# Deckelplatine.net
KiCad netlist of a schematic drawn in EAGLE
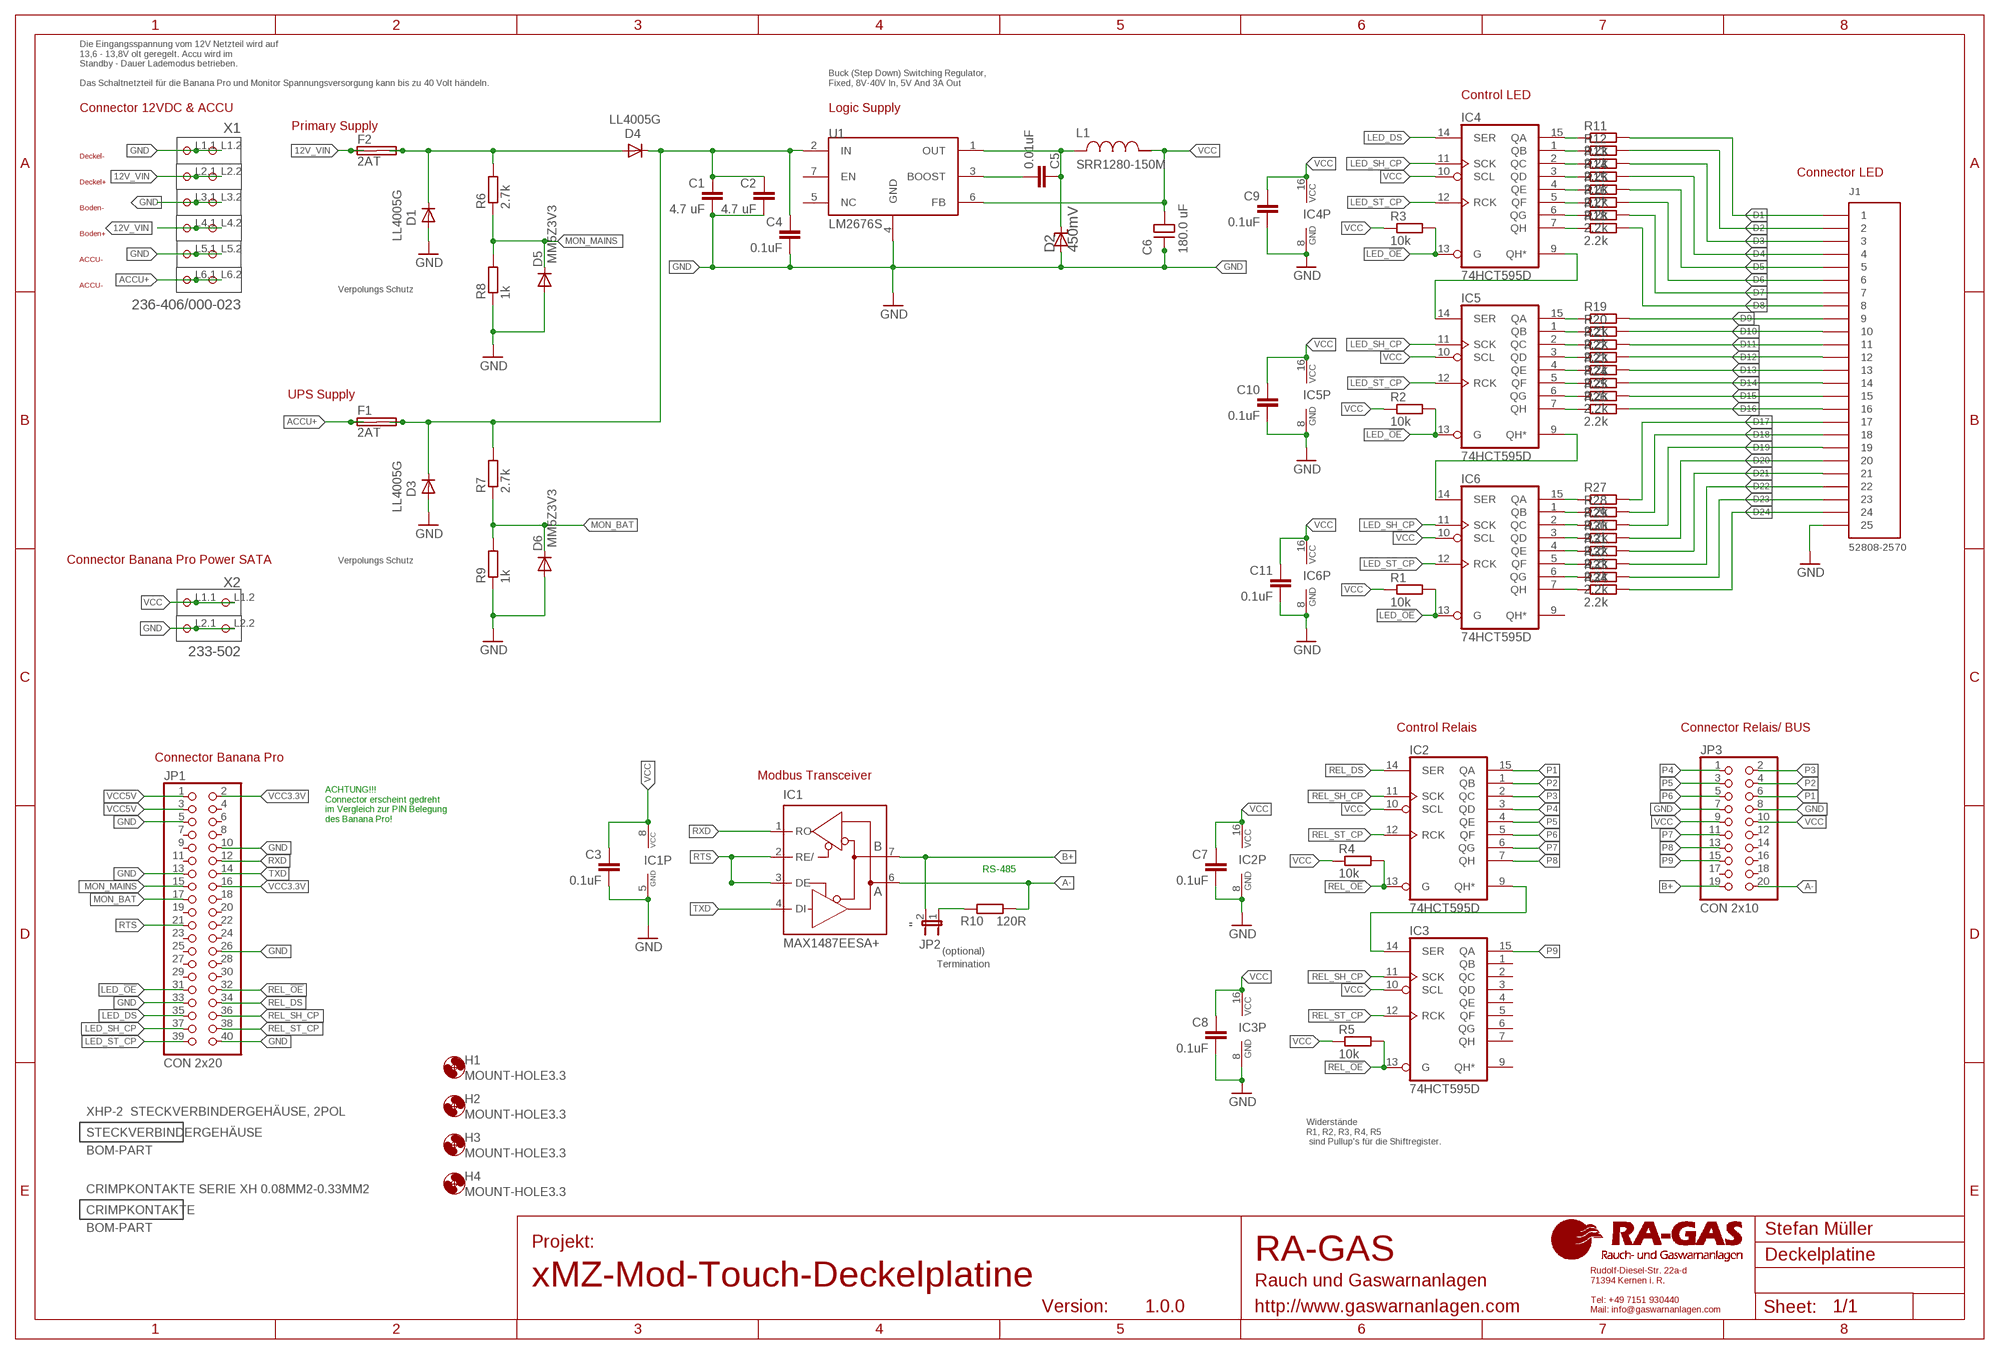
[diagram p0: schematic, sheet 1]

(export (version "E")
  (design (tool "Eeschema 10.0.6"))
  (components
    (comp (ref "C1")
      (value "4.7 uF")
      (footprint "eagle-import:GRM21BR61E475MA12L")
      (fields (field (name "MANUFACTURER_PART_NUMBER") "GRM21BR61E475MA12L") (field (name "MF") "MURATA"))
      (libsource (lib "eagle-import") (part "GRM21BR61E475MA12L"))
    )
    (comp (ref "C2")
      (value "4.7 uF")
      (footprint "eagle-import:GRM21BR61E475MA12L")
      (fields (field (name "MANUFACTURER_PART_NUMBER") "GRM21BR61E475MA12L") (field (name "MF") "MURATA"))
      (libsource (lib "eagle-import") (part "GRM21BR61E475MA12L"))
    )
    (comp (ref "C3")
      (value "0.1uF")
      (footprint "eagle-import:C0603")
      (fields
        (field (name "MF") "KEMET")
        (field (name "MPN") "C0603C104K8RACTU")
        (field (name "PARTNO") "SMD TAN.0,1/35")
      )
      (libsource (lib "eagle-import") (part "C-EUC0603"))
    )
    (comp (ref "C4")
      (value "0.1uF")
      (footprint "eagle-import:0805")
      (fields (field (name "MANUFACTURER_PART_NUMBER") "08053C104KAT2A") (field (name "MF") "AVX"))
      (libsource (lib "eagle-import") (part "08053C104KAT2A"))
    )
    (comp (ref "C5")
      (value "0.01uF")
      (footprint "eagle-import:GRM216R71H103KA01D")
      (fields (field (name "MANUFACTURER_PART_NUMBER") "GRM216R71H103KA01D") (field (name "MF") "MURATA"))
      (libsource (lib "eagle-import") (part "GRM216R71H103KA01D"))
    )
    (comp (ref "C6")
      (value "180.0 uF")
      (footprint "eagle-import:SM_RADIAL_10MM")
      (fields
        (field (name "MF") "PANASONIC ELECTRONIC COMPONENTS")
        (field (name "MPN") "16SVP180MX")
        (field (name "PARTNO") "RAD FC 560/35")
      )
      (libsource (lib "eagle-import") (part "16SVP180MSM_RADIAL_10MM"))
    )
    (comp (ref "C7")
      (value "0.1uF")
      (footprint "eagle-import:C0603")
      (fields
        (field (name "MF") "KEMET")
        (field (name "MPN") "C0603C104K8RACTU")
        (field (name "PARTNO") "SMD TAN.0,1/35")
      )
      (libsource (lib "eagle-import") (part "C-EUC0603"))
    )
    (comp (ref "C8")
      (value "0.1uF")
      (footprint "eagle-import:C0603")
      (fields
        (field (name "MF") "KEMET")
        (field (name "MPN") "C0603C104K8RACTU")
        (field (name "PARTNO") "SMD TAN.0,1/35")
      )
      (libsource (lib "eagle-import") (part "C-EUC0603"))
    )
    (comp (ref "C9")
      (value "0.1uF")
      (footprint "eagle-import:C0603")
      (fields
        (field (name "MF") "KEMET")
        (field (name "MPN") "C0603C104K8RACTU")
        (field (name "PARTNO") "SMD TAN.0,1/35")
      )
      (libsource (lib "eagle-import") (part "C-EUC0603"))
    )
    (comp (ref "C10")
      (value "0.1uF")
      (footprint "eagle-import:C0603")
      (fields
        (field (name "MF") "KEMET")
        (field (name "MPN") "C0603C104K8RACTU")
        (field (name "PARTNO") "SMD TAN.0,1/35")
      )
      (libsource (lib "eagle-import") (part "C-EUC0603"))
    )
    (comp (ref "C11")
      (value "0.1uF")
      (footprint "eagle-import:C0603")
      (fields
        (field (name "MF") "KEMET")
        (field (name "MPN") "C0603C104K8RACTU")
        (field (name "PARTNO") "SMD TAN.0,1/35")
      )
      (libsource (lib "eagle-import") (part "C-EUC0603"))
    )
    (comp (ref "D1")
      (value "LL4005G")
      (footprint "eagle-import:MELF-MLL41")
      (fields (field (name "MF") "TAIWAN SEMICONDUCTOR"))
      (libsource (lib "eagle-import") (part "diode_DIODE-MELF-MLL41"))
    )
    (comp (ref "D2")
      (value "450mV")
      (footprint "eagle-import:SMB")
      (fields (field (name "MANUFACTURER_PART_NUMBER") "B340LB-13-F") (field (name "MF") "DIODES INC."))
      (libsource (lib "eagle-import") (part "B340LB-13-F"))
    )
    (comp (ref "D3")
      (value "LL4005G")
      (footprint "eagle-import:MELF-MLL41")
      (fields (field (name "MF") "TAIWAN SEMICONDUCTOR"))
      (libsource (lib "eagle-import") (part "diode_DIODE-MELF-MLL41"))
    )
    (comp (ref "D4")
      (value "LL4005G")
      (footprint "eagle-import:MELF-MLL41")
      (fields (field (name "MF") "TAIWAN SEMICONDUCTOR"))
      (libsource (lib "eagle-import") (part "diode_DIODE-MELF-MLL41"))
    )
    (comp (ref "D5")
      (value "MM5Z3V3")
      (footprint "eagle-import:SOD523")
      (fields (field (name "MF") "FAIRCHILD SEMICONDUCTOR"))
      (libsource (lib "eagle-import") (part "DIODE-SOD523"))
    )
    (comp (ref "D6")
      (value "MM5Z3V3")
      (footprint "eagle-import:SOD523")
      (fields (field (name "MF") "FAIRCHILD SEMICONDUCTOR"))
      (libsource (lib "eagle-import") (part "DIODE-SOD523"))
    )
    (comp (ref "F1")
      (value "2AT")
      (footprint "eagle-import:01110005MR")
      (fields
        (field (name "MF") "LITTELFUSE")
        (field (name "MPN") "01110005MR")
        (field (name "OC_FARNELL") "2413914")
      )
      (libsource (lib "eagle-import") (part "01110005MR"))
    )
    (comp (ref "F2")
      (value "2AT")
      (footprint "eagle-import:01110005MR")
      (fields
        (field (name "MF") "LITTELFUSE")
        (field (name "MPN") "01110005MR")
        (field (name "OC_FARNELL") "2413914")
      )
      (libsource (lib "eagle-import") (part "01110005MR"))
    )
    (comp (ref "H1")
      (value "MOUNT-HOLE3.3")
      (footprint "eagle-import:3,3")
      (libsource (lib "eagle-import") (part "MOUNT-HOLE3.3"))
    )
    (comp (ref "H2")
      (value "MOUNT-HOLE3.3")
      (footprint "eagle-import:3,3")
      (libsource (lib "eagle-import") (part "MOUNT-HOLE3.3"))
    )
    (comp (ref "H3")
      (value "MOUNT-HOLE3.3")
      (footprint "eagle-import:3,3")
      (libsource (lib "eagle-import") (part "MOUNT-HOLE3.3"))
    )
    (comp (ref "H4")
      (value "MOUNT-HOLE3.3")
      (footprint "eagle-import:3,3")
      (libsource (lib "eagle-import") (part "MOUNT-HOLE3.3"))
    )
    (comp (ref "IC1")
      (value "MAX1487EESA+")
      (footprint "eagle-import:SO08")
      (fields
        (field (name "MF") "MAXIM")
        (field (name "MPN") "MAX481CSA")
        (field (name "MF_1") "MAXIM INTEGRATED PRODUCTS")
        (field (name "MPN_1") "MAX1487EESA+.")
        (field (name "OC_FARNELL") "1593310")
        (field (name "PARTNO") "MAX481CSA")
        (field (name "OC_FARNELL_ALTERNATIVE") "8452210")
      )
      (libsource (lib "eagle-import") (part "MAX481CSA"))
    )
    (comp (ref "IC2")
      (value "74HCT595D")
      (footprint "eagle-import:SO16")
      (fields
        (field (name "MF") "NXP")
        (field (name "MPN") "74HCT595D")
        (field (name "OC_FARNELL") "2098004")
        (field (name "PARTNO") "SMD HC 595")
      )
      (libsource (lib "eagle-import") (part "74595DHCT"))
    )
    (comp (ref "IC3")
      (value "74HCT595D")
      (footprint "eagle-import:SO16")
      (fields
        (field (name "MF") "NXP")
        (field (name "MPN") "74HCT595D")
        (field (name "OC_FARNELL") "2098004")
        (field (name "PARTNO") "SMD HC 595")
      )
      (libsource (lib "eagle-import") (part "74595DHCT"))
    )
    (comp (ref "IC4")
      (value "74HCT595D")
      (footprint "eagle-import:SO16")
      (fields
        (field (name "MF") "NXP")
        (field (name "MPN") "74HCT595D")
        (field (name "OC_FARNELL") "2098004")
        (field (name "PARTNO") "SMD HC 595")
      )
      (libsource (lib "eagle-import") (part "74595DHCT"))
    )
    (comp (ref "IC5")
      (value "74HCT595D")
      (footprint "eagle-import:SO16")
      (fields
        (field (name "MF") "NXP")
        (field (name "MPN") "74HCT595D")
        (field (name "OC_FARNELL") "2098004")
        (field (name "PARTNO") "SMD HC 595")
      )
      (libsource (lib "eagle-import") (part "74595DHCT"))
    )
    (comp (ref "IC6")
      (value "74HCT595D")
      (footprint "eagle-import:SO16")
      (fields
        (field (name "MF") "NXP")
        (field (name "MPN") "74HCT595D")
        (field (name "OC_FARNELL") "2098004")
        (field (name "PARTNO") "SMD HC 595")
      )
      (libsource (lib "eagle-import") (part "74595DHCT"))
    )
    (comp (ref "J1")
      (value "52808-2570")
      (footprint "eagle-import:52808-2570")
      (fields (field (name "MF") "MOLEX"))
      (libsource (lib "eagle-import") (part "52808-2570"))
    )
    (comp (ref "JP1")
      (value "CON 2x20")
      (footprint "eagle-import:2X20")
      (fields (field (name "MF") "HARWIN") (field (name "MPN") "M20-6112045"))
      (libsource (lib "eagle-import") (part "PINHD-2X20"))
    )
    (comp (ref "JP2")
      (value "''")
      (footprint "eagle-import:JP1")
      (fields (field (name "MF") "TE CONNECTIVITY / AMP") (field (name "MPN") "825433-2"))
      (libsource (lib "eagle-import") (part "JP1E"))
    )
    (comp (ref "JP3")
      (value "CON 2x10")
      (footprint "eagle-import:2X10")
      (fields (field (name "MF") "TE CONNECTIVITY / AMP") (field (name "MPN") "5103308-5"))
      (libsource (lib "eagle-import") (part "PINHD-2X10"))
    )
    (comp (ref "L1")
      (value "SRR1280-150M")
      (footprint "eagle-import:SRR1280")
      (fields (field (name "MF") "COILCRAFT") (field (name "MPN") "MSS1278-153MLD"))
      (libsource (lib "eagle-import") (part "SRR1280-150M"))
    )
    (comp (ref "R1")
      (value "10k")
      (footprint "eagle-import:R0603")
      (fields (field (name "MF") "TE CONNECTIVITY / NEOHM") (field (name "MPN") "CPF0603B10KE1"))
      (libsource (lib "eagle-import") (part "R-EU_R0603"))
    )
    (comp (ref "R2")
      (value "10k")
      (footprint "eagle-import:R0603")
      (fields (field (name "MF") "TE CONNECTIVITY / NEOHM") (field (name "MPN") "CPF0603B10KE1"))
      (libsource (lib "eagle-import") (part "R-EU_R0603"))
    )
    (comp (ref "R3")
      (value "10k")
      (footprint "eagle-import:R0603")
      (fields (field (name "MF") "TE CONNECTIVITY / NEOHM") (field (name "MPN") "CPF0603B10KE1"))
      (libsource (lib "eagle-import") (part "R-EU_R0603"))
    )
    (comp (ref "R4")
      (value "10k")
      (footprint "eagle-import:R0603")
      (fields (field (name "MF") "TE CONNECTIVITY / NEOHM") (field (name "MPN") "CPF0603B10KE1"))
      (libsource (lib "eagle-import") (part "R-EU_R0603"))
    )
    (comp (ref "R5")
      (value "10k")
      (footprint "eagle-import:R0603")
      (fields (field (name "MF") "TE CONNECTIVITY / NEOHM") (field (name "MPN") "CPF0603B10KE1"))
      (libsource (lib "eagle-import") (part "R-EU_R0603"))
    )
    (comp (ref "R6")
      (value "2.7k")
      (footprint "eagle-import:R0603")
      (fields (field (name "MF") "VISHAY") (field (name "MPN") "CRCW08052K70FKEA"))
      (libsource (lib "eagle-import") (part "R-EU_R0603"))
    )
    (comp (ref "R7")
      (value "2.7k")
      (footprint "eagle-import:R0603")
      (fields (field (name "MF") "VISHAY") (field (name "MPN") "CRCW08052K70FKEA"))
      (libsource (lib "eagle-import") (part "R-EU_R0603"))
    )
    (comp (ref "R8")
      (value "1k")
      (footprint "eagle-import:R0603")
      (fields (field (name "MF") "YAGEO (PHYCOMP)") (field (name "MPN") "RC0603FR-071KL."))
      (libsource (lib "eagle-import") (part "R-EU_R0603"))
    )
    (comp (ref "R9")
      (value "1k")
      (footprint "eagle-import:R0603")
      (fields (field (name "MF") "YAGEO (PHYCOMP)") (field (name "MPN") "RC0603FR-071KL."))
      (libsource (lib "eagle-import") (part "R-EU_R0603"))
    )
    (comp (ref "R10")
      (value "120R")
      (footprint "eagle-import:R1206")
      (fields (field (name "MF") "TE CONNECTIVITY") (field (name "MPN") "CRGH1206F120R"))
      (libsource (lib "eagle-import") (part "rcl_R-EU_R1206"))
    )
    (comp (ref "R11")
      (value "2.2k")
      (footprint "eagle-import:R0603")
      (fields
        (field (name "MF") "YAGEO (PHYCOMP)")
        (field (name "MPN") "RC0603FR-072K2L.")
        (field (name "PARTNO") "SMD-0603 2,2K")
      )
      (libsource (lib "eagle-import") (part "R-EU_R0603"))
    )
    (comp (ref "R12")
      (value "2.2k")
      (footprint "eagle-import:R0603")
      (fields
        (field (name "MF") "YAGEO (PHYCOMP)")
        (field (name "MPN") "RC0603FR-072K2L.")
        (field (name "PARTNO") "SMD-0603 2,2K")
      )
      (libsource (lib "eagle-import") (part "R-EU_R0603"))
    )
    (comp (ref "R13")
      (value "2.2k")
      (footprint "eagle-import:R0603")
      (fields
        (field (name "MF") "YAGEO (PHYCOMP)")
        (field (name "MPN") "RC0603FR-072K2L.")
        (field (name "PARTNO") "SMD-0603 2,2K")
      )
      (libsource (lib "eagle-import") (part "R-EU_R0603"))
    )
    (comp (ref "R14")
      (value "2.2k")
      (footprint "eagle-import:R0603")
      (fields
        (field (name "MF") "YAGEO (PHYCOMP)")
        (field (name "MPN") "RC0603FR-072K2L.")
        (field (name "PARTNO") "SMD-0603 2,2K")
      )
      (libsource (lib "eagle-import") (part "R-EU_R0603"))
    )
    (comp (ref "R15")
      (value "2.2k")
      (footprint "eagle-import:R0603")
      (fields
        (field (name "MF") "YAGEO (PHYCOMP)")
        (field (name "MPN") "RC0603FR-072K2L.")
        (field (name "PARTNO") "SMD-0603 2,2K")
      )
      (libsource (lib "eagle-import") (part "R-EU_R0603"))
    )
    (comp (ref "R16")
      (value "2.2k")
      (footprint "eagle-import:R0603")
      (fields
        (field (name "MF") "YAGEO (PHYCOMP)")
        (field (name "MPN") "RC0603FR-072K2L.")
        (field (name "PARTNO") "SMD-0603 2,2K")
      )
      (libsource (lib "eagle-import") (part "R-EU_R0603"))
    )
    (comp (ref "R17")
      (value "2.2k")
      (footprint "eagle-import:R0603")
      (fields
        (field (name "MF") "YAGEO (PHYCOMP)")
        (field (name "MPN") "RC0603FR-072K2L.")
        (field (name "PARTNO") "SMD-0603 2,2K")
      )
      (libsource (lib "eagle-import") (part "R-EU_R0603"))
    )
    (comp (ref "R18")
      (value "2.2k")
      (footprint "eagle-import:R0603")
      (fields
        (field (name "MF") "YAGEO (PHYCOMP)")
        (field (name "MPN") "RC0603FR-072K2L.")
        (field (name "PARTNO") "SMD-0603 2,2K")
      )
      (libsource (lib "eagle-import") (part "R-EU_R0603"))
    )
    (comp (ref "R19")
      (value "2.2k")
      (footprint "eagle-import:R0603")
      (fields
        (field (name "MF") "YAGEO (PHYCOMP)")
        (field (name "MPN") "RC0603FR-072K2L.")
        (field (name "PARTNO") "SMD-0603 2,2K")
      )
      (libsource (lib "eagle-import") (part "R-EU_R0603"))
    )
    (comp (ref "R20")
      (value "2.2k")
      (footprint "eagle-import:R0603")
      (fields
        (field (name "MF") "YAGEO (PHYCOMP)")
        (field (name "MPN") "RC0603FR-072K2L.")
        (field (name "PARTNO") "SMD-0603 2,2K")
      )
      (libsource (lib "eagle-import") (part "R-EU_R0603"))
    )
    (comp (ref "R21")
      (value "2.2k")
      (footprint "eagle-import:R0603")
      (fields
        (field (name "MF") "YAGEO (PHYCOMP)")
        (field (name "MPN") "RC0603FR-072K2L.")
        (field (name "PARTNO") "SMD-0603 2,2K")
      )
      (libsource (lib "eagle-import") (part "R-EU_R0603"))
    )
    (comp (ref "R22")
      (value "2.2k")
      (footprint "eagle-import:R0603")
      (fields
        (field (name "MF") "YAGEO (PHYCOMP)")
        (field (name "MPN") "RC0603FR-072K2L.")
        (field (name "PARTNO") "SMD-0603 2,2K")
      )
      (libsource (lib "eagle-import") (part "R-EU_R0603"))
    )
    (comp (ref "R23")
      (value "2.2k")
      (footprint "eagle-import:R0603")
      (fields
        (field (name "MF") "YAGEO (PHYCOMP)")
        (field (name "MPN") "RC0603FR-072K2L.")
        (field (name "PARTNO") "SMD-0603 2,2K")
      )
      (libsource (lib "eagle-import") (part "R-EU_R0603"))
    )
    (comp (ref "R24")
      (value "2.2k")
      (footprint "eagle-import:R0603")
      (fields
        (field (name "MF") "YAGEO (PHYCOMP)")
        (field (name "MPN") "RC0603FR-072K2L.")
        (field (name "PARTNO") "SMD-0603 2,2K")
      )
      (libsource (lib "eagle-import") (part "R-EU_R0603"))
    )
    (comp (ref "R25")
      (value "2.2k")
      (footprint "eagle-import:R0603")
      (fields
        (field (name "MF") "YAGEO (PHYCOMP)")
        (field (name "MPN") "RC0603FR-072K2L.")
        (field (name "PARTNO") "SMD-0603 2,2K")
      )
      (libsource (lib "eagle-import") (part "R-EU_R0603"))
    )
    (comp (ref "R26")
      (value "2.2k")
      (footprint "eagle-import:R0603")
      (fields
        (field (name "MF") "YAGEO (PHYCOMP)")
        (field (name "MPN") "RC0603FR-072K2L.")
        (field (name "PARTNO") "SMD-0603 2,2K")
      )
      (libsource (lib "eagle-import") (part "R-EU_R0603"))
    )
    (comp (ref "R27")
      (value "2.2k")
      (footprint "eagle-import:R0603")
      (fields
        (field (name "MF") "YAGEO (PHYCOMP)")
        (field (name "MPN") "RC0603FR-072K2L.")
        (field (name "PARTNO") "SMD-0603 2,2K")
      )
      (libsource (lib "eagle-import") (part "R-EU_R0603"))
    )
    (comp (ref "R28")
      (value "2.2k")
      (footprint "eagle-import:R0603")
      (fields
        (field (name "MF") "YAGEO (PHYCOMP)")
        (field (name "MPN") "RC0603FR-072K2L.")
        (field (name "PARTNO") "SMD-0603 2,2K")
      )
      (libsource (lib "eagle-import") (part "R-EU_R0603"))
    )
    (comp (ref "R29")
      (value "2.2k")
      (footprint "eagle-import:R0603")
      (fields
        (field (name "MF") "YAGEO (PHYCOMP)")
        (field (name "MPN") "RC0603FR-072K2L.")
        (field (name "PARTNO") "SMD-0603 2,2K")
      )
      (libsource (lib "eagle-import") (part "R-EU_R0603"))
    )
    (comp (ref "R30")
      (value "2.2k")
      (footprint "eagle-import:R0603")
      (fields
        (field (name "MF") "YAGEO (PHYCOMP)")
        (field (name "MPN") "RC0603FR-072K2L.")
        (field (name "PARTNO") "SMD-0603 2,2K")
      )
      (libsource (lib "eagle-import") (part "R-EU_R0603"))
    )
    (comp (ref "R31")
      (value "2.2k")
      (footprint "eagle-import:R0603")
      (fields
        (field (name "MF") "YAGEO (PHYCOMP)")
        (field (name "MPN") "RC0603FR-072K2L.")
        (field (name "PARTNO") "SMD-0603 2,2K")
      )
      (libsource (lib "eagle-import") (part "R-EU_R0603"))
    )
    (comp (ref "R32")
      (value "2.2k")
      (footprint "eagle-import:R0603")
      (fields
        (field (name "MF") "YAGEO (PHYCOMP)")
        (field (name "MPN") "RC0603FR-072K2L.")
        (field (name "PARTNO") "SMD-0603 2,2K")
      )
      (libsource (lib "eagle-import") (part "R-EU_R0603"))
    )
    (comp (ref "R33")
      (value "2.2k")
      (footprint "eagle-import:R0603")
      (fields
        (field (name "MF") "YAGEO (PHYCOMP)")
        (field (name "MPN") "RC0603FR-072K2L.")
        (field (name "PARTNO") "SMD-0603 2,2K")
      )
      (libsource (lib "eagle-import") (part "R-EU_R0603"))
    )
    (comp (ref "R34")
      (value "2.2k")
      (footprint "eagle-import:R0603")
      (fields
        (field (name "MF") "YAGEO (PHYCOMP)")
        (field (name "MPN") "RC0603FR-072K2L.")
        (field (name "PARTNO") "SMD-0603 2,2K")
      )
      (libsource (lib "eagle-import") (part "R-EU_R0603"))
    )
    (comp (ref "U1")
      (value "LM2676S")
      (footprint "eagle-import:TO-263-7")
      (fields (field (name "MF") "TEXAS INSTRUMENTS") (field (name "MPN") "LM2676S-5.0/NOPB"))
      (libsource (lib "eagle-import") (part "LM2676S"))
    )
    (comp (ref "X1")
      (value "236-406/000-023")
      (footprint "eagle-import:P-236-406")
      (fields (field (name "MF") "WAGO") (field (name "MPN") "236-406"))
      (libsource (lib "eagle-import") (part "236-406/000-023"))
    )
    (comp (ref "X2")
      (value "233-502")
      (footprint "eagle-import:P-233-502")
      (fields (field (name "MF") "WAGO") (field (name "MPN") "233-502."))
      (libsource (lib "eagle-import") (part "233-502"))
    )
  )
  (nets
    (net (code "1") (name "/LED_~{OE}") (class "Default")
      (node (ref "IC4") (pin "13") (pinfunction "G_13") (pintype "input"))
      (node (ref "IC5") (pin "13") (pinfunction "G_13") (pintype "input"))
      (node (ref "IC6") (pin "13") (pinfunction "G_13") (pintype "input"))
      (node (ref "JP1") (pin "31") (pinfunction "31_31") (pintype "passive"))
      (node (ref "R1") (pin "2") (pinfunction "2_2") (pintype "passive"))
      (node (ref "R2") (pin "2") (pinfunction "2_2") (pintype "passive"))
      (node (ref "R3") (pin "2") (pinfunction "2_2") (pintype "passive"))
    )
    (net (code "2") (name "/REL_~{OE}") (class "Default")
      (node (ref "IC2") (pin "13") (pinfunction "G_13") (pintype "input"))
      (node (ref "IC3") (pin "13") (pinfunction "G_13") (pintype "input"))
      (node (ref "JP1") (pin "32") (pinfunction "32_32") (pintype "passive"))
      (node (ref "R4") (pin "2") (pinfunction "2_2") (pintype "passive"))
      (node (ref "R5") (pin "2") (pinfunction "2_2") (pintype "passive"))
    )
    (net (code "3") (name "12V_VIN") (class "Default")
      (node (ref "F2") (pin "1A") (pinfunction "1A_1A") (pintype "passive"))
      (node (ref "F2") (pin "1B") (pinfunction "1B_1B") (pintype "passive"))
      (node (ref "X1") (pin "L2.1") (pinfunction "P2.1_L2.1") (pintype "bidirectional"))
      (node (ref "X1") (pin "L2.2") (pinfunction "P2.2_L2.2") (pintype "bidirectional"))
      (node (ref "X1") (pin "L4.1") (pinfunction "P4.1_L4.1") (pintype "bidirectional"))
      (node (ref "X1") (pin "L4.2") (pinfunction "P4.2_L4.2") (pintype "bidirectional"))
    )
    (net (code "4") (name "A-") (class "Default")
      (node (ref "IC1") (pin "6") (pinfunction "A_6") (pintype "passive"))
      (node (ref "JP3") (pin "20") (pinfunction "20_20") (pintype "passive"))
      (node (ref "R10") (pin "2") (pinfunction "2_2") (pintype "passive"))
    )
    (net (code "5") (name "ACCU+") (class "Default")
      (node (ref "F1") (pin "1A") (pinfunction "1A_1A") (pintype "passive"))
      (node (ref "F1") (pin "1B") (pinfunction "1B_1B") (pintype "passive"))
      (node (ref "X1") (pin "L6.1") (pinfunction "P6.1_L6.1") (pintype "bidirectional"))
      (node (ref "X1") (pin "L6.2") (pinfunction "P6.2_L6.2") (pintype "bidirectional"))
    )
    (net (code "6") (name "B+") (class "Default")
      (node (ref "IC1") (pin "7") (pinfunction "B_7") (pintype "passive"))
      (node (ref "JP2") (pin "2") (pinfunction "2_2") (pintype "passive"))
      (node (ref "JP3") (pin "19") (pinfunction "19_19") (pintype "passive"))
    )
    (net (code "7") (name "D1") (class "Default")
      (node (ref "J1") (pin "1") (pinfunction "1_1") (pintype "bidirectional"))
      (node (ref "R11") (pin "2") (pinfunction "2_2") (pintype "passive"))
    )
    (net (code "8") (name "D2") (class "Default")
      (node (ref "J1") (pin "2") (pinfunction "2_2") (pintype "bidirectional"))
      (node (ref "R12") (pin "2") (pinfunction "2_2") (pintype "passive"))
    )
    (net (code "9") (name "D3") (class "Default")
      (node (ref "J1") (pin "3") (pinfunction "3_3") (pintype "bidirectional"))
      (node (ref "R13") (pin "2") (pinfunction "2_2") (pintype "passive"))
    )
    (net (code "10") (name "D4") (class "Default")
      (node (ref "J1") (pin "4") (pinfunction "4_4") (pintype "bidirectional"))
      (node (ref "R14") (pin "2") (pinfunction "2_2") (pintype "passive"))
    )
    (net (code "11") (name "D5") (class "Default")
      (node (ref "J1") (pin "5") (pinfunction "5_5") (pintype "bidirectional"))
      (node (ref "R15") (pin "2") (pinfunction "2_2") (pintype "passive"))
    )
    (net (code "12") (name "D6") (class "Default")
      (node (ref "J1") (pin "6") (pinfunction "6_6") (pintype "bidirectional"))
      (node (ref "R16") (pin "2") (pinfunction "2_2") (pintype "passive"))
    )
    (net (code "13") (name "D7") (class "Default")
      (node (ref "J1") (pin "7") (pinfunction "7_7") (pintype "bidirectional"))
      (node (ref "R17") (pin "2") (pinfunction "2_2") (pintype "passive"))
    )
    (net (code "14") (name "D8") (class "Default")
      (node (ref "J1") (pin "8") (pinfunction "8_8") (pintype "bidirectional"))
      (node (ref "R18") (pin "2") (pinfunction "2_2") (pintype "passive"))
    )
    (net (code "15") (name "D9") (class "Default")
      (node (ref "J1") (pin "9") (pinfunction "9_9") (pintype "bidirectional"))
      (node (ref "R19") (pin "2") (pinfunction "2_2") (pintype "passive"))
    )
    (net (code "16") (name "D10") (class "Default")
      (node (ref "J1") (pin "10") (pinfunction "10_10") (pintype "bidirectional"))
      (node (ref "R20") (pin "2") (pinfunction "2_2") (pintype "passive"))
    )
    (net (code "17") (name "D11") (class "Default")
      (node (ref "J1") (pin "11") (pinfunction "11_11") (pintype "bidirectional"))
      (node (ref "R21") (pin "2") (pinfunction "2_2") (pintype "passive"))
    )
    (net (code "18") (name "D12") (class "Default")
      (node (ref "J1") (pin "12") (pinfunction "12_12") (pintype "bidirectional"))
      (node (ref "R22") (pin "2") (pinfunction "2_2") (pintype "passive"))
    )
    (net (code "19") (name "D13") (class "Default")
      (node (ref "J1") (pin "13") (pinfunction "13_13") (pintype "bidirectional"))
      (node (ref "R23") (pin "2") (pinfunction "2_2") (pintype "passive"))
    )
    (net (code "20") (name "D14") (class "Default")
      (node (ref "J1") (pin "14") (pinfunction "14_14") (pintype "bidirectional"))
      (node (ref "R24") (pin "2") (pinfunction "2_2") (pintype "passive"))
    )
    (net (code "21") (name "D15") (class "Default")
      (node (ref "J1") (pin "15") (pinfunction "15_15") (pintype "bidirectional"))
      (node (ref "R25") (pin "2") (pinfunction "2_2") (pintype "passive"))
    )
    (net (code "22") (name "D16") (class "Default")
      (node (ref "J1") (pin "16") (pinfunction "16_16") (pintype "bidirectional"))
      (node (ref "R26") (pin "2") (pinfunction "2_2") (pintype "passive"))
    )
    (net (code "23") (name "D17") (class "Default")
      (node (ref "J1") (pin "17") (pinfunction "17_17") (pintype "bidirectional"))
      (node (ref "R27") (pin "2") (pinfunction "2_2") (pintype "passive"))
    )
    (net (code "24") (name "D18") (class "Default")
      (node (ref "J1") (pin "18") (pinfunction "18_18") (pintype "bidirectional"))
      (node (ref "R28") (pin "2") (pinfunction "2_2") (pintype "passive"))
    )
    (net (code "25") (name "D19") (class "Default")
      (node (ref "J1") (pin "19") (pinfunction "19_19") (pintype "bidirectional"))
      (node (ref "R29") (pin "2") (pinfunction "2_2") (pintype "passive"))
    )
    (net (code "26") (name "D20") (class "Default")
      (node (ref "J1") (pin "20") (pinfunction "20_20") (pintype "bidirectional"))
      (node (ref "R30") (pin "2") (pinfunction "2_2") (pintype "passive"))
    )
    (net (code "27") (name "D21") (class "Default")
      (node (ref "J1") (pin "21") (pinfunction "21_21") (pintype "bidirectional"))
      (node (ref "R31") (pin "2") (pinfunction "2_2") (pintype "passive"))
    )
    (net (code "28") (name "D22") (class "Default")
      (node (ref "J1") (pin "22") (pinfunction "22_22") (pintype "bidirectional"))
      (node (ref "R32") (pin "2") (pinfunction "2_2") (pintype "passive"))
    )
    (net (code "29") (name "D23") (class "Default")
      (node (ref "J1") (pin "23") (pinfunction "23_23") (pintype "bidirectional"))
      (node (ref "R33") (pin "2") (pinfunction "2_2") (pintype "passive"))
    )
    (net (code "30") (name "D24") (class "Default")
      (node (ref "J1") (pin "24") (pinfunction "24_24") (pintype "bidirectional"))
      (node (ref "R34") (pin "2") (pinfunction "2_2") (pintype "passive"))
    )
    (net (code "31") (name "GND") (class "Default")
      (node (ref "C1") (pin "2") (pinfunction "2_2") (pintype "passive"))
      (node (ref "C10") (pin "2") (pinfunction "2_2") (pintype "passive"))
      (node (ref "C11") (pin "2") (pinfunction "2_2") (pintype "passive"))
      (node (ref "C2") (pin "2") (pinfunction "2_2") (pintype "passive"))
      (node (ref "C3") (pin "2") (pinfunction "2_2") (pintype "passive"))
      (node (ref "C4") (pin "2") (pinfunction "2_2") (pintype "passive"))
      (node (ref "C6") (pin "2") (pinfunction "-_2") (pintype "passive"))
      (node (ref "C7") (pin "2") (pinfunction "2_2") (pintype "passive"))
      (node (ref "C8") (pin "2") (pinfunction "2_2") (pintype "passive"))
      (node (ref "C9") (pin "2") (pinfunction "2_2") (pintype "passive"))
      (node (ref "D1") (pin "A") (pinfunction "A_A") (pintype "passive"))
      (node (ref "D2") (pin "A") (pinfunction "A_A") (pintype "passive"))
      (node (ref "D3") (pin "A") (pinfunction "A_A") (pintype "passive"))
      (node (ref "D5") (pin "A") (pinfunction "A_A") (pintype "passive"))
      (node (ref "D6") (pin "A") (pinfunction "A_A") (pintype "passive"))
      (node (ref "IC1") (pin "5") (pinfunction "GND_5") (pintype "power_in"))
      (node (ref "IC2") (pin "8") (pinfunction "GND_8") (pintype "power_in"))
      (node (ref "IC3") (pin "8") (pinfunction "GND_8") (pintype "power_in"))
      (node (ref "IC4") (pin "8") (pinfunction "GND_8") (pintype "power_in"))
      (node (ref "IC5") (pin "8") (pinfunction "GND_8") (pintype "power_in"))
      (node (ref "IC6") (pin "8") (pinfunction "GND_8") (pintype "power_in"))
      (node (ref "J1") (pin "25") (pinfunction "25_25") (pintype "bidirectional"))
      (node (ref "JP1") (pin "10") (pinfunction "10_10") (pintype "passive"))
      (node (ref "JP1") (pin "13") (pinfunction "13_13") (pintype "passive"))
      (node (ref "JP1") (pin "26") (pinfunction "26_26") (pintype "passive"))
      (node (ref "JP1") (pin "33") (pinfunction "33_33") (pintype "passive"))
      (node (ref "JP1") (pin "40") (pinfunction "40_40") (pintype "passive"))
      (node (ref "JP1") (pin "5") (pinfunction "5_5") (pintype "passive"))
      (node (ref "JP3") (pin "7") (pinfunction "7_7") (pintype "passive"))
      (node (ref "JP3") (pin "8") (pinfunction "8_8") (pintype "passive"))
      (node (ref "R8") (pin "1") (pinfunction "1_1") (pintype "passive"))
      (node (ref "R9") (pin "1") (pinfunction "1_1") (pintype "passive"))
      (node (ref "U1") (pin "4") (pinfunction "GND_4") (pintype "power_in"))
      (node (ref "X1") (pin "L1.1") (pinfunction "P1.1_L1.1") (pintype "bidirectional"))
      (node (ref "X1") (pin "L1.2") (pinfunction "P1.2_L1.2") (pintype "bidirectional"))
      (node (ref "X1") (pin "L3.1") (pinfunction "P3.1_L3.1") (pintype "bidirectional"))
      (node (ref "X1") (pin "L3.2") (pinfunction "P3.2_L3.2") (pintype "bidirectional"))
      (node (ref "X1") (pin "L5.1") (pinfunction "P5.1_L5.1") (pintype "bidirectional"))
      (node (ref "X1") (pin "L5.2") (pinfunction "P5.2_L5.2") (pintype "bidirectional"))
      (node (ref "X2") (pin "L2.1") (pinfunction "P2.1_L2.1") (pintype "bidirectional"))
      (node (ref "X2") (pin "L2.2") (pinfunction "P2.2_L2.2") (pintype "bidirectional"))
    )
    (net (code "32") (name "LED_DS") (class "Default")
      (node (ref "IC4") (pin "14") (pinfunction "SER_14") (pintype "input"))
      (node (ref "JP1") (pin "35") (pinfunction "35_35") (pintype "passive"))
    )
    (net (code "33") (name "LED_SH_CP") (class "Default")
      (node (ref "IC4") (pin "11") (pinfunction "SCK_11") (pintype "input"))
      (node (ref "IC5") (pin "11") (pinfunction "SCK_11") (pintype "input"))
      (node (ref "IC6") (pin "11") (pinfunction "SCK_11") (pintype "input"))
      (node (ref "JP1") (pin "37") (pinfunction "37_37") (pintype "passive"))
    )
    (net (code "34") (name "LED_ST_CP") (class "Default")
      (node (ref "IC4") (pin "12") (pinfunction "RCK_12") (pintype "input"))
      (node (ref "IC5") (pin "12") (pinfunction "RCK_12") (pintype "input"))
      (node (ref "IC6") (pin "12") (pinfunction "RCK_12") (pintype "input"))
      (node (ref "JP1") (pin "39") (pinfunction "39_39") (pintype "passive"))
    )
    (net (code "35") (name "MON_BAT") (class "Default")
      (node (ref "D6") (pin "C") (pinfunction "C_C") (pintype "passive"))
      (node (ref "JP1") (pin "17") (pinfunction "17_17") (pintype "passive"))
      (node (ref "R7") (pin "1") (pinfunction "1_1") (pintype "passive"))
      (node (ref "R9") (pin "2") (pinfunction "2_2") (pintype "passive"))
    )
    (net (code "36") (name "MON_MAINS") (class "Default")
      (node (ref "D5") (pin "C") (pinfunction "C_C") (pintype "passive"))
      (node (ref "JP1") (pin "15") (pinfunction "15_15") (pintype "passive"))
      (node (ref "R6") (pin "1") (pinfunction "1_1") (pintype "passive"))
      (node (ref "R8") (pin "2") (pinfunction "2_2") (pintype "passive"))
    )
    (net (code "37") (name "Net-(D1-PadC)") (class "Default")
      (node (ref "D1") (pin "C") (pinfunction "C_C") (pintype "passive"))
      (node (ref "D4") (pin "A") (pinfunction "A_A") (pintype "passive"))
      (node (ref "F2") (pin "2A") (pinfunction "2A_2A") (pintype "passive"))
      (node (ref "F2") (pin "2B") (pinfunction "2B_2B") (pintype "passive"))
      (node (ref "R6") (pin "2") (pinfunction "2_2") (pintype "passive"))
    )
    (net (code "38") (name "Net-(IC2A-QH*)") (class "Default")
      (node (ref "IC2") (pin "9") (pinfunction "QH*_9") (pintype "tri_state"))
      (node (ref "IC3") (pin "14") (pinfunction "SER_14") (pintype "input"))
    )
    (net (code "39") (name "Net-(IC4A-QA)") (class "Default")
      (node (ref "IC4") (pin "15") (pinfunction "QA_15") (pintype "tri_state"))
      (node (ref "R11") (pin "1") (pinfunction "1_1") (pintype "passive"))
    )
    (net (code "40") (name "Net-(IC4A-QB)") (class "Default")
      (node (ref "IC4") (pin "1") (pinfunction "QB_1") (pintype "tri_state"))
      (node (ref "R12") (pin "1") (pinfunction "1_1") (pintype "passive"))
    )
    (net (code "41") (name "Net-(IC4A-QC)") (class "Default")
      (node (ref "IC4") (pin "2") (pinfunction "QC_2") (pintype "tri_state"))
      (node (ref "R13") (pin "1") (pinfunction "1_1") (pintype "passive"))
    )
    (net (code "42") (name "Net-(IC4A-QD)") (class "Default")
      (node (ref "IC4") (pin "3") (pinfunction "QD_3") (pintype "tri_state"))
      (node (ref "R14") (pin "1") (pinfunction "1_1") (pintype "passive"))
    )
    (net (code "43") (name "Net-(IC4A-QE)") (class "Default")
      (node (ref "IC4") (pin "4") (pinfunction "QE_4") (pintype "tri_state"))
      (node (ref "R15") (pin "1") (pinfunction "1_1") (pintype "passive"))
    )
    (net (code "44") (name "Net-(IC4A-QF)") (class "Default")
      (node (ref "IC4") (pin "5") (pinfunction "QF_5") (pintype "tri_state"))
      (node (ref "R16") (pin "1") (pinfunction "1_1") (pintype "passive"))
    )
    (net (code "45") (name "Net-(IC4A-QG)") (class "Default")
      (node (ref "IC4") (pin "6") (pinfunction "QG_6") (pintype "tri_state"))
      (node (ref "R17") (pin "1") (pinfunction "1_1") (pintype "passive"))
    )
    (net (code "46") (name "Net-(IC4A-QH)") (class "Default")
      (node (ref "IC4") (pin "7") (pinfunction "QH_7") (pintype "tri_state"))
      (node (ref "R18") (pin "1") (pinfunction "1_1") (pintype "passive"))
    )
    (net (code "47") (name "Net-(IC4A-QH*)") (class "Default")
      (node (ref "IC4") (pin "9") (pinfunction "QH*_9") (pintype "tri_state"))
      (node (ref "IC5") (pin "14") (pinfunction "SER_14") (pintype "input"))
    )
    (net (code "48") (name "Net-(IC5A-QA)") (class "Default")
      (node (ref "IC5") (pin "15") (pinfunction "QA_15") (pintype "tri_state"))
      (node (ref "R19") (pin "1") (pinfunction "1_1") (pintype "passive"))
    )
    (net (code "49") (name "Net-(IC5A-QB)") (class "Default")
      (node (ref "IC5") (pin "1") (pinfunction "QB_1") (pintype "tri_state"))
      (node (ref "R20") (pin "1") (pinfunction "1_1") (pintype "passive"))
    )
    (net (code "50") (name "Net-(IC5A-QC)") (class "Default")
      (node (ref "IC5") (pin "2") (pinfunction "QC_2") (pintype "tri_state"))
      (node (ref "R21") (pin "1") (pinfunction "1_1") (pintype "passive"))
    )
    (net (code "51") (name "Net-(IC5A-QD)") (class "Default")
      (node (ref "IC5") (pin "3") (pinfunction "QD_3") (pintype "tri_state"))
      (node (ref "R22") (pin "1") (pinfunction "1_1") (pintype "passive"))
    )
    (net (code "52") (name "Net-(IC5A-QE)") (class "Default")
      (node (ref "IC5") (pin "4") (pinfunction "QE_4") (pintype "tri_state"))
      (node (ref "R23") (pin "1") (pinfunction "1_1") (pintype "passive"))
    )
    (net (code "53") (name "Net-(IC5A-QF)") (class "Default")
      (node (ref "IC5") (pin "5") (pinfunction "QF_5") (pintype "tri_state"))
      (node (ref "R24") (pin "1") (pinfunction "1_1") (pintype "passive"))
    )
    (net (code "54") (name "Net-(IC5A-QG)") (class "Default")
      (node (ref "IC5") (pin "6") (pinfunction "QG_6") (pintype "tri_state"))
      (node (ref "R25") (pin "1") (pinfunction "1_1") (pintype "passive"))
    )
    (net (code "55") (name "Net-(IC5A-QH)") (class "Default")
      (node (ref "IC5") (pin "7") (pinfunction "QH_7") (pintype "tri_state"))
      (node (ref "R26") (pin "1") (pinfunction "1_1") (pintype "passive"))
    )
    (net (code "56") (name "Net-(IC5A-QH*)") (class "Default")
      (node (ref "IC5") (pin "9") (pinfunction "QH*_9") (pintype "tri_state"))
      (node (ref "IC6") (pin "14") (pinfunction "SER_14") (pintype "input"))
    )
    (net (code "57") (name "Net-(IC6A-QA)") (class "Default")
      (node (ref "IC6") (pin "15") (pinfunction "QA_15") (pintype "tri_state"))
      (node (ref "R27") (pin "1") (pinfunction "1_1") (pintype "passive"))
    )
    (net (code "58") (name "Net-(IC6A-QB)") (class "Default")
      (node (ref "IC6") (pin "1") (pinfunction "QB_1") (pintype "tri_state"))
      (node (ref "R28") (pin "1") (pinfunction "1_1") (pintype "passive"))
    )
    (net (code "59") (name "Net-(IC6A-QC)") (class "Default")
      (node (ref "IC6") (pin "2") (pinfunction "QC_2") (pintype "tri_state"))
      (node (ref "R29") (pin "1") (pinfunction "1_1") (pintype "passive"))
    )
    (net (code "60") (name "Net-(IC6A-QD)") (class "Default")
      (node (ref "IC6") (pin "3") (pinfunction "QD_3") (pintype "tri_state"))
      (node (ref "R30") (pin "1") (pinfunction "1_1") (pintype "passive"))
    )
    (net (code "61") (name "Net-(IC6A-QE)") (class "Default")
      (node (ref "IC6") (pin "4") (pinfunction "QE_4") (pintype "tri_state"))
      (node (ref "R31") (pin "1") (pinfunction "1_1") (pintype "passive"))
    )
    (net (code "62") (name "Net-(IC6A-QF)") (class "Default")
      (node (ref "IC6") (pin "5") (pinfunction "QF_5") (pintype "tri_state"))
      (node (ref "R32") (pin "1") (pinfunction "1_1") (pintype "passive"))
    )
    (net (code "63") (name "Net-(IC6A-QG)") (class "Default")
      (node (ref "IC6") (pin "6") (pinfunction "QG_6") (pintype "tri_state"))
      (node (ref "R33") (pin "1") (pinfunction "1_1") (pintype "passive"))
    )
    (net (code "64") (name "Net-(IC6A-QH)") (class "Default")
      (node (ref "IC6") (pin "7") (pinfunction "QH_7") (pintype "tri_state"))
      (node (ref "R34") (pin "1") (pinfunction "1_1") (pintype "passive"))
    )
    (net (code "65") (name "Net-(JP2-Pad1)") (class "Default")
      (node (ref "JP2") (pin "1") (pinfunction "1_1") (pintype "passive"))
      (node (ref "R10") (pin "1") (pinfunction "1_1") (pintype "passive"))
    )
    (net (code "66") (name "Net-(U1-BOOST)") (class "Default")
      (node (ref "C5") (pin "2") (pinfunction "2_2") (pintype "passive"))
      (node (ref "U1") (pin "3") (pinfunction "BOOST_3") (pintype "bidirectional"))
    )
    (net (code "67") (name "Net-(U1-IN)") (class "Default")
      (node (ref "C1") (pin "1") (pinfunction "1_1") (pintype "passive"))
      (node (ref "C2") (pin "1") (pinfunction "1_1") (pintype "passive"))
      (node (ref "C4") (pin "1") (pinfunction "1_1") (pintype "passive"))
      (node (ref "D3") (pin "C") (pinfunction "C_C") (pintype "passive"))
      (node (ref "D4") (pin "C") (pinfunction "C_C") (pintype "passive"))
      (node (ref "F1") (pin "2A") (pinfunction "2A_2A") (pintype "passive"))
      (node (ref "F1") (pin "2B") (pinfunction "2B_2B") (pintype "passive"))
      (node (ref "R7") (pin "2") (pinfunction "2_2") (pintype "passive"))
      (node (ref "U1") (pin "2") (pinfunction "IN_2") (pintype "power_in"))
    )
    (net (code "68") (name "Net-(U1-OUT)") (class "Default")
      (node (ref "C5") (pin "1") (pinfunction "1_1") (pintype "passive"))
      (node (ref "D2") (pin "C") (pinfunction "C_C") (pintype "passive"))
      (node (ref "L1") (pin "1") (pinfunction "1_1") (pintype "passive"))
      (node (ref "U1") (pin "1") (pinfunction "OUT_1") (pintype "bidirectional"))
    )
    (net (code "69") (name "P1") (class "Default")
      (node (ref "IC2") (pin "15") (pinfunction "QA_15") (pintype "tri_state"))
      (node (ref "JP3") (pin "6") (pinfunction "6_6") (pintype "passive"))
    )
    (net (code "70") (name "P2") (class "Default")
      (node (ref "IC2") (pin "1") (pinfunction "QB_1") (pintype "tri_state"))
      (node (ref "JP3") (pin "4") (pinfunction "4_4") (pintype "passive"))
    )
    (net (code "71") (name "P3") (class "Default")
      (node (ref "IC2") (pin "2") (pinfunction "QC_2") (pintype "tri_state"))
      (node (ref "JP3") (pin "2") (pinfunction "2_2") (pintype "passive"))
    )
    (net (code "72") (name "P4") (class "Default")
      (node (ref "IC2") (pin "3") (pinfunction "QD_3") (pintype "tri_state"))
      (node (ref "JP3") (pin "1") (pinfunction "1_1") (pintype "passive"))
    )
    (net (code "73") (name "P5") (class "Default")
      (node (ref "IC2") (pin "4") (pinfunction "QE_4") (pintype "tri_state"))
      (node (ref "JP3") (pin "3") (pinfunction "3_3") (pintype "passive"))
    )
    (net (code "74") (name "P6") (class "Default")
      (node (ref "IC2") (pin "5") (pinfunction "QF_5") (pintype "tri_state"))
      (node (ref "JP3") (pin "5") (pinfunction "5_5") (pintype "passive"))
    )
    (net (code "75") (name "P7") (class "Default")
      (node (ref "IC2") (pin "6") (pinfunction "QG_6") (pintype "tri_state"))
      (node (ref "JP3") (pin "11") (pinfunction "11_11") (pintype "passive"))
    )
    (net (code "76") (name "P8") (class "Default")
      (node (ref "IC2") (pin "7") (pinfunction "QH_7") (pintype "tri_state"))
      (node (ref "JP3") (pin "13") (pinfunction "13_13") (pintype "passive"))
    )
    (net (code "77") (name "P9") (class "Default")
      (node (ref "IC3") (pin "15") (pinfunction "QA_15") (pintype "tri_state"))
      (node (ref "JP3") (pin "15") (pinfunction "15_15") (pintype "passive"))
    )
    (net (code "78") (name "REL_DS") (class "Default")
      (node (ref "IC2") (pin "14") (pinfunction "SER_14") (pintype "input"))
      (node (ref "JP1") (pin "34") (pinfunction "34_34") (pintype "passive"))
    )
    (net (code "79") (name "REL_SH_CP") (class "Default")
      (node (ref "IC2") (pin "11") (pinfunction "SCK_11") (pintype "input"))
      (node (ref "IC3") (pin "11") (pinfunction "SCK_11") (pintype "input"))
      (node (ref "JP1") (pin "36") (pinfunction "36_36") (pintype "passive"))
    )
    (net (code "80") (name "REL_ST_CP") (class "Default")
      (node (ref "IC2") (pin "12") (pinfunction "RCK_12") (pintype "input"))
      (node (ref "IC3") (pin "12") (pinfunction "RCK_12") (pintype "input"))
      (node (ref "JP1") (pin "38") (pinfunction "38_38") (pintype "passive"))
    )
    (net (code "81") (name "RTS") (class "Default")
      (node (ref "IC1") (pin "2") (pinfunction "RE/_2") (pintype "input"))
      (node (ref "IC1") (pin "3") (pinfunction "DE_3") (pintype "input"))
      (node (ref "JP1") (pin "21") (pinfunction "21_21") (pintype "passive"))
    )
    (net (code "82") (name "RXD") (class "Default")
      (node (ref "IC1") (pin "1") (pinfunction "RO_1") (pintype "output"))
      (node (ref "JP1") (pin "12") (pinfunction "12_12") (pintype "passive"))
    )
    (net (code "83") (name "TXD") (class "Default")
      (node (ref "IC1") (pin "4") (pinfunction "DI_4") (pintype "input"))
      (node (ref "JP1") (pin "14") (pinfunction "14_14") (pintype "passive"))
    )
    (net (code "84") (name "VCC") (class "Default")
      (node (ref "C10") (pin "1") (pinfunction "1_1") (pintype "passive"))
      (node (ref "C11") (pin "1") (pinfunction "1_1") (pintype "passive"))
      (node (ref "C3") (pin "1") (pinfunction "1_1") (pintype "passive"))
      (node (ref "C6") (pin "1") (pinfunction "+_1") (pintype "passive"))
      (node (ref "C7") (pin "1") (pinfunction "1_1") (pintype "passive"))
      (node (ref "C8") (pin "1") (pinfunction "1_1") (pintype "passive"))
      (node (ref "C9") (pin "1") (pinfunction "1_1") (pintype "passive"))
      (node (ref "IC1") (pin "8") (pinfunction "VCC_8") (pintype "power_in"))
      (node (ref "IC2") (pin "10") (pinfunction "SCL_10") (pintype "input"))
      (node (ref "IC2") (pin "16") (pinfunction "VCC_16") (pintype "power_in"))
      (node (ref "IC3") (pin "10") (pinfunction "SCL_10") (pintype "input"))
      (node (ref "IC3") (pin "16") (pinfunction "VCC_16") (pintype "power_in"))
      (node (ref "IC4") (pin "10") (pinfunction "SCL_10") (pintype "input"))
      (node (ref "IC4") (pin "16") (pinfunction "VCC_16") (pintype "power_in"))
      (node (ref "IC5") (pin "10") (pinfunction "SCL_10") (pintype "input"))
      (node (ref "IC5") (pin "16") (pinfunction "VCC_16") (pintype "power_in"))
      (node (ref "IC6") (pin "10") (pinfunction "SCL_10") (pintype "input"))
      (node (ref "IC6") (pin "16") (pinfunction "VCC_16") (pintype "power_in"))
      (node (ref "JP3") (pin "10") (pinfunction "10_10") (pintype "passive"))
      (node (ref "JP3") (pin "9") (pinfunction "9_9") (pintype "passive"))
      (node (ref "L1") (pin "2") (pinfunction "2_2") (pintype "passive"))
      (node (ref "R1") (pin "1") (pinfunction "1_1") (pintype "passive"))
      (node (ref "R2") (pin "1") (pinfunction "1_1") (pintype "passive"))
      (node (ref "R3") (pin "1") (pinfunction "1_1") (pintype "passive"))
      (node (ref "R4") (pin "1") (pinfunction "1_1") (pintype "passive"))
      (node (ref "R5") (pin "1") (pinfunction "1_1") (pintype "passive"))
      (node (ref "U1") (pin "6") (pinfunction "FB_6") (pintype "bidirectional"))
      (node (ref "X2") (pin "L1.1") (pinfunction "P1.1_L1.1") (pintype "bidirectional"))
      (node (ref "X2") (pin "L1.2") (pinfunction "P1.2_L1.2") (pintype "bidirectional"))
    )
    (net (code "85") (name "VCC3.3V") (class "Default")
      (node (ref "JP1") (pin "16") (pinfunction "16_16") (pintype "passive"))
      (node (ref "JP1") (pin "2") (pinfunction "2_2") (pintype "passive"))
    )
    (net (code "86") (name "VCC5V") (class "Default")
      (node (ref "JP1") (pin "1") (pinfunction "1_1") (pintype "passive"))
      (node (ref "JP1") (pin "3") (pinfunction "3_3") (pintype "passive"))
    )
    (net (code "87") (name "unconnected-(IC3A-QB-Pad1)") (class "Default")
      (node (ref "IC3") (pin "1") (pinfunction "QB_1") (pintype "tri_state"))
    )
    (net (code "88") (name "unconnected-(IC3A-QC-Pad2)") (class "Default")
      (node (ref "IC3") (pin "2") (pinfunction "QC_2") (pintype "tri_state"))
    )
    (net (code "89") (name "unconnected-(IC3A-QD-Pad3)") (class "Default")
      (node (ref "IC3") (pin "3") (pinfunction "QD_3") (pintype "tri_state"))
    )
    (net (code "90") (name "unconnected-(IC3A-QE-Pad4)") (class "Default")
      (node (ref "IC3") (pin "4") (pinfunction "QE_4") (pintype "tri_state"))
    )
    (net (code "91") (name "unconnected-(IC3A-QF-Pad5)") (class "Default")
      (node (ref "IC3") (pin "5") (pinfunction "QF_5") (pintype "tri_state"))
    )
    (net (code "92") (name "unconnected-(IC3A-QG-Pad6)") (class "Default")
      (node (ref "IC3") (pin "6") (pinfunction "QG_6") (pintype "tri_state"))
    )
    (net (code "93") (name "unconnected-(IC3A-QH*-Pad9)") (class "Default")
      (node (ref "IC3") (pin "9") (pinfunction "QH*_9") (pintype "tri_state"))
    )
    (net (code "94") (name "unconnected-(IC3A-QH-Pad7)") (class "Default")
      (node (ref "IC3") (pin "7") (pinfunction "QH_7") (pintype "tri_state"))
    )
    (net (code "95") (name "unconnected-(IC6A-QH*-Pad9)") (class "Default")
      (node (ref "IC6") (pin "9") (pinfunction "QH*_9") (pintype "tri_state"))
    )
    (net (code "96") (name "unconnected-(JP1-Pad4)") (class "Default")
      (node (ref "JP1") (pin "4") (pinfunction "4_4") (pintype "passive"))
    )
    (net (code "97") (name "unconnected-(JP1-Pad6)") (class "Default")
      (node (ref "JP1") (pin "6") (pinfunction "6_6") (pintype "passive"))
    )
    (net (code "98") (name "unconnected-(JP1-Pad7)") (class "Default")
      (node (ref "JP1") (pin "7") (pinfunction "7_7") (pintype "passive"))
    )
    (net (code "99") (name "unconnected-(JP1-Pad8)") (class "Default")
      (node (ref "JP1") (pin "8") (pinfunction "8_8") (pintype "passive"))
    )
    (net (code "100") (name "unconnected-(JP1-Pad9)") (class "Default")
      (node (ref "JP1") (pin "9") (pinfunction "9_9") (pintype "passive"))
    )
    (net (code "101") (name "unconnected-(JP1-Pad11)") (class "Default")
      (node (ref "JP1") (pin "11") (pinfunction "11_11") (pintype "passive"))
    )
    (net (code "102") (name "unconnected-(JP1-Pad18)") (class "Default")
      (node (ref "JP1") (pin "18") (pinfunction "18_18") (pintype "passive"))
    )
    (net (code "103") (name "unconnected-(JP1-Pad19)") (class "Default")
      (node (ref "JP1") (pin "19") (pinfunction "19_19") (pintype "passive"))
    )
    (net (code "104") (name "unconnected-(JP1-Pad20)") (class "Default")
      (node (ref "JP1") (pin "20") (pinfunction "20_20") (pintype "passive"))
    )
    (net (code "105") (name "unconnected-(JP1-Pad22)") (class "Default")
      (node (ref "JP1") (pin "22") (pinfunction "22_22") (pintype "passive"))
    )
    (net (code "106") (name "unconnected-(JP1-Pad23)") (class "Default")
      (node (ref "JP1") (pin "23") (pinfunction "23_23") (pintype "passive"))
    )
    (net (code "107") (name "unconnected-(JP1-Pad24)") (class "Default")
      (node (ref "JP1") (pin "24") (pinfunction "24_24") (pintype "passive"))
    )
    (net (code "108") (name "unconnected-(JP1-Pad25)") (class "Default")
      (node (ref "JP1") (pin "25") (pinfunction "25_25") (pintype "passive"))
    )
    (net (code "109") (name "unconnected-(JP1-Pad27)") (class "Default")
      (node (ref "JP1") (pin "27") (pinfunction "27_27") (pintype "passive"))
    )
    (net (code "110") (name "unconnected-(JP1-Pad28)") (class "Default")
      (node (ref "JP1") (pin "28") (pinfunction "28_28") (pintype "passive"))
    )
    (net (code "111") (name "unconnected-(JP1-Pad29)") (class "Default")
      (node (ref "JP1") (pin "29") (pinfunction "29_29") (pintype "passive"))
    )
    (net (code "112") (name "unconnected-(JP1-Pad30)") (class "Default")
      (node (ref "JP1") (pin "30") (pinfunction "30_30") (pintype "passive"))
    )
    (net (code "113") (name "unconnected-(JP3-Pad12)") (class "Default")
      (node (ref "JP3") (pin "12") (pinfunction "12_12") (pintype "passive"))
    )
    (net (code "114") (name "unconnected-(JP3-Pad14)") (class "Default")
      (node (ref "JP3") (pin "14") (pinfunction "14_14") (pintype "passive"))
    )
    (net (code "115") (name "unconnected-(JP3-Pad16)") (class "Default")
      (node (ref "JP3") (pin "16") (pinfunction "16_16") (pintype "passive"))
    )
    (net (code "116") (name "unconnected-(JP3-Pad17)") (class "Default")
      (node (ref "JP3") (pin "17") (pinfunction "17_17") (pintype "passive"))
    )
    (net (code "117") (name "unconnected-(JP3-Pad18)") (class "Default")
      (node (ref "JP3") (pin "18") (pinfunction "18_18") (pintype "passive"))
    )
    (net (code "118") (name "unconnected-(U1-EN-Pad7)") (class "Default")
      (node (ref "U1") (pin "7") (pinfunction "EN_7") (pintype "bidirectional"))
    )
    (net (code "119") (name "unconnected-(U1-NC-Pad5)") (class "Default")
      (node (ref "U1") (pin "5") (pinfunction "NC_5") (pintype "no_connect"))
    )
  )
)
